# FPGAPower.net
KiCad netlist of a schematic drawn in Altium Designer
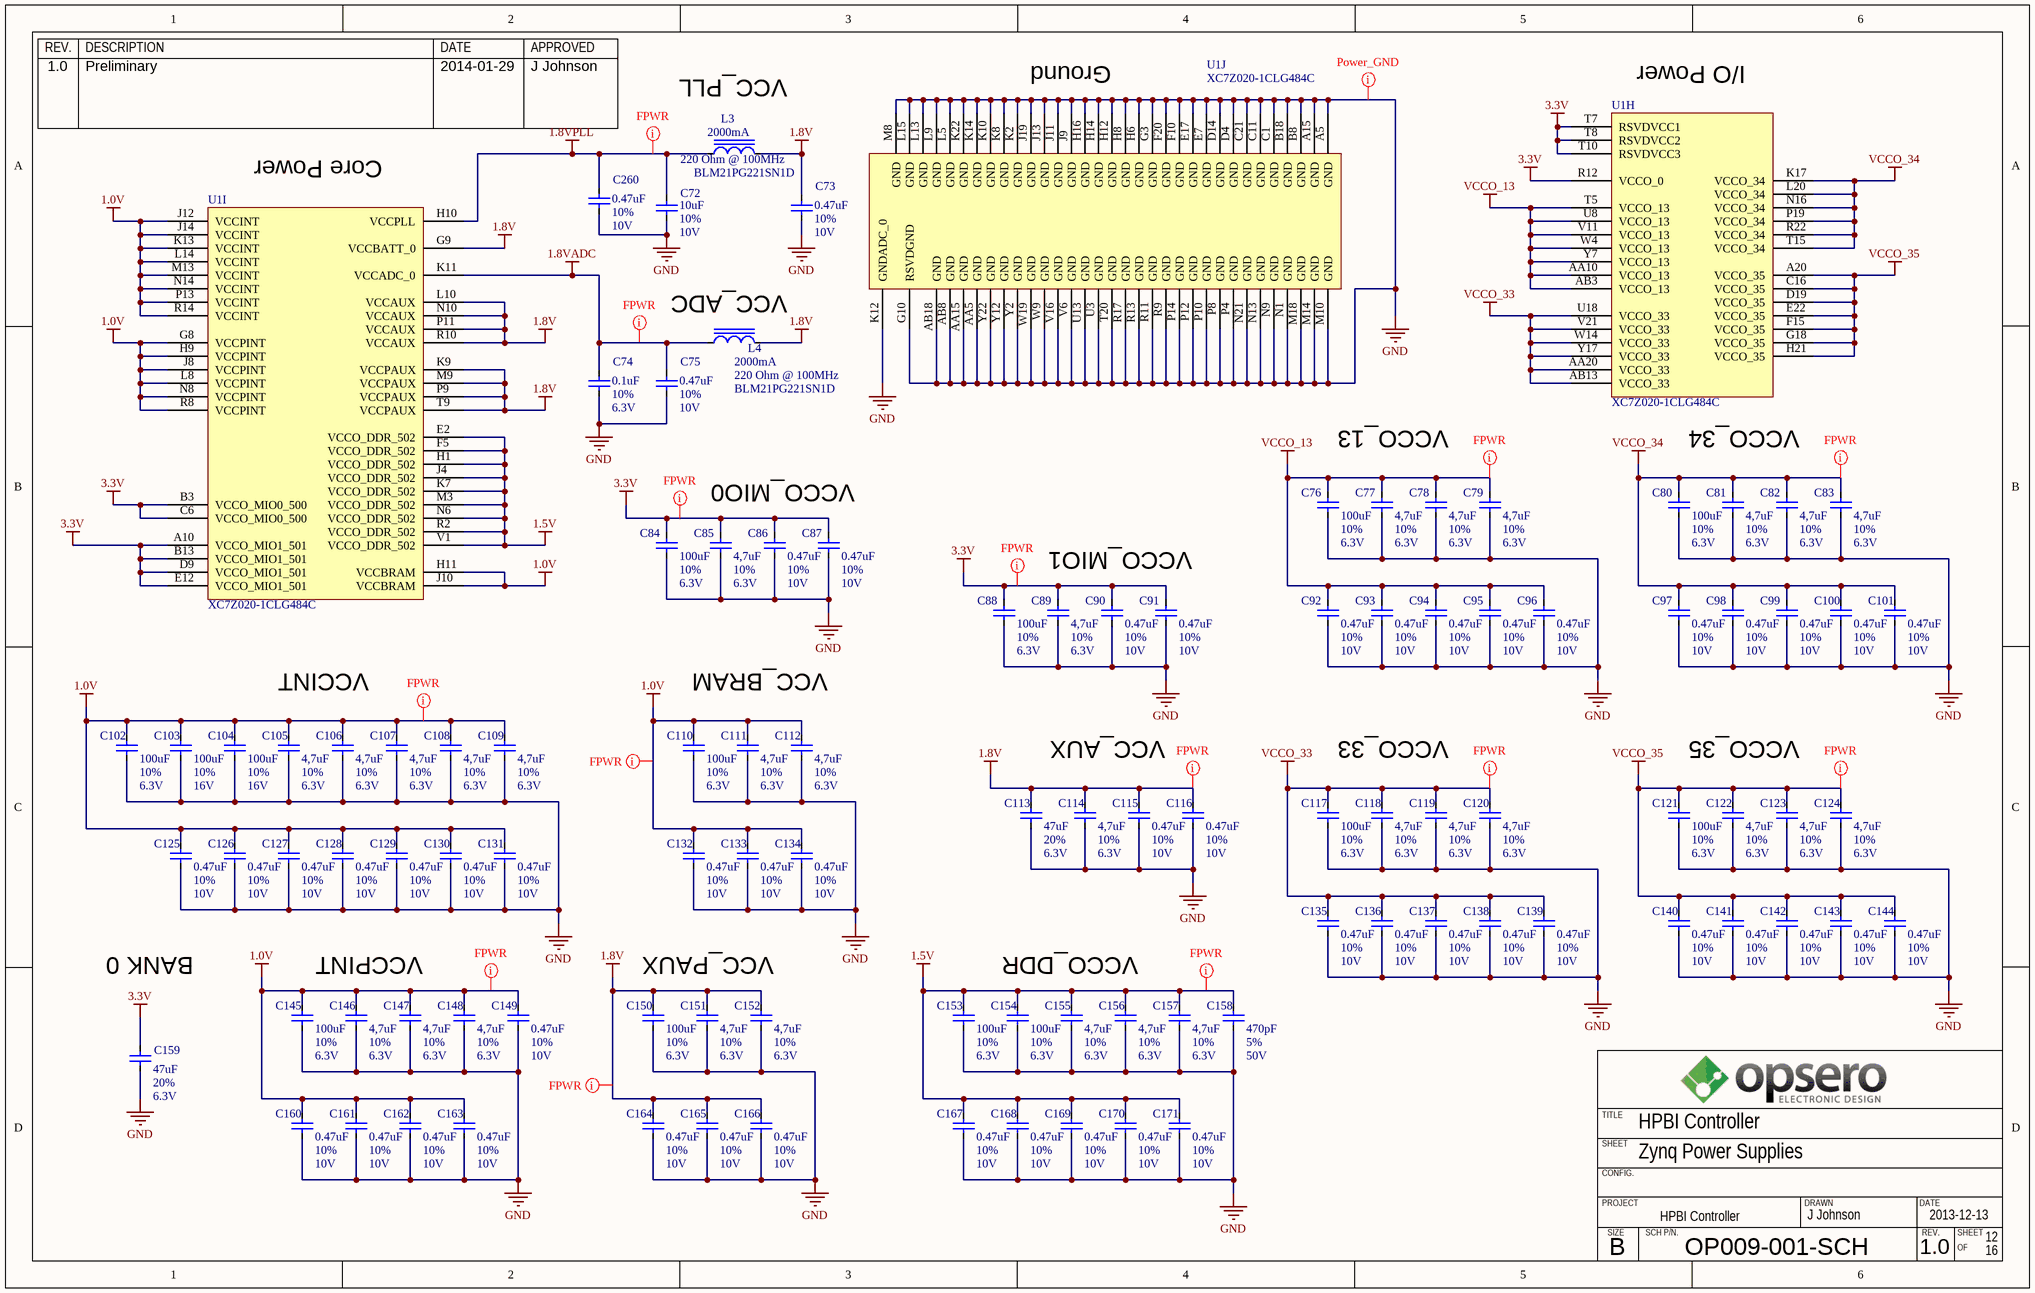
[diagram p0: FPGAPower.SchDoc]

(export (version "E")
  (design (tool "Eeschema 10.0.6"))
  (components
    (comp (ref "C72")
      (value "10uF")
      (footprint "CAPC1608X38N")
      (description "Capacitor ceramic, X5R, 10uF, 10V, 10%, -55 to +85 C, EIA0603")
      (fields
        (field (name "TOLERANCE") "10%")
        (field (name "VOLTAGE") "10V")
        (field (name "Comment") "CAPACITOR_NP_TYPE1")
      )
      (libsource (lib "parts") (part "CAPACITOR_NP_TYPE1"))
    )
    (comp (ref "C73")
      (value "0.47uF")
      (footprint "CAPC1005X55N")
      (description "Capacitor ceramic, X5R, 0.47uF, 10V, 10%, -55 to +85 C, EIA0402")
      (fields
        (field (name "TOLERANCE") "10%")
        (field (name "VOLTAGE") "10V")
        (field (name "Comment") "CAPACITOR_NP_TYPE1")
      )
      (libsource (lib "parts") (part "CAPACITOR_NP_TYPE1"))
    )
    (comp (ref "C74")
      (value "0.1uF")
      (footprint "CAPC0603X33N")
      (description "Capacitor ceramic, X5R, 0.1uF, 6.3V, 10%, -55 to +125 C, EIA0201")
      (fields
        (field (name "TOLERANCE") "10%")
        (field (name "VOLTAGE") "6.3V")
        (field (name "Comment") "CAPACITOR_NP_TYPE1")
      )
      (libsource (lib "parts") (part "CAPACITOR_NP_TYPE1"))
    )
    (comp (ref "C75")
      (value "0.47uF")
      (footprint "CAPC1005X55N")
      (description "Capacitor ceramic, X5R, 0.47uF, 10V, 10%, -55 to +85 C, EIA0402")
      (fields
        (field (name "TOLERANCE") "10%")
        (field (name "VOLTAGE") "10V")
        (field (name "Comment") "CAPACITOR_NP_TYPE1")
      )
      (libsource (lib "parts") (part "CAPACITOR_NP_TYPE1"))
    )
    (comp (ref "C76")
      (value "100uF")
      (footprint "CAPC3225X250N")
      (description "Capacitor ceramic, X5R, 100uF, 6.3V, 10%, -55 to +85 C, EIA1210")
      (fields
        (field (name "TOLERANCE") "10%")
        (field (name "VOLTAGE") "6.3V")
        (field (name "Comment") "CAPACITOR_NP_TYPE1")
      )
      (libsource (lib "parts") (part "CAPACITOR_NP_TYPE1"))
    )
    (comp (ref "C77")
      (value "4,7uF")
      (footprint "CAPC1005X33N")
      (description "Capacitor ceramic, X5R, 4,7uF, 6.3V, 10%, -55 to +85 C, EIA0402")
      (fields
        (field (name "TOLERANCE") "10%")
        (field (name "VOLTAGE") "6.3V")
        (field (name "Comment") "CAPACITOR_NP_TYPE1")
      )
      (libsource (lib "parts") (part "CAPACITOR_NP_TYPE1"))
    )
    (comp (ref "C78")
      (value "4,7uF")
      (footprint "CAPC1005X33N")
      (description "Capacitor ceramic, X5R, 4,7uF, 6.3V, 10%, -55 to +85 C, EIA0402")
      (fields
        (field (name "TOLERANCE") "10%")
        (field (name "VOLTAGE") "6.3V")
        (field (name "Comment") "CAPACITOR_NP_TYPE1")
      )
      (libsource (lib "parts") (part "CAPACITOR_NP_TYPE1"))
    )
    (comp (ref "C79")
      (value "4,7uF")
      (footprint "CAPC1005X33N")
      (description "Capacitor ceramic, X5R, 4,7uF, 6.3V, 10%, -55 to +85 C, EIA0402")
      (fields
        (field (name "TOLERANCE") "10%")
        (field (name "VOLTAGE") "6.3V")
        (field (name "Comment") "CAPACITOR_NP_TYPE1")
      )
      (libsource (lib "parts") (part "CAPACITOR_NP_TYPE1"))
    )
    (comp (ref "C80")
      (value "100uF")
      (footprint "CAPC3225X250N")
      (description "Capacitor ceramic, X5R, 100uF, 6.3V, 10%, -55 to +85 C, EIA1210")
      (fields
        (field (name "TOLERANCE") "10%")
        (field (name "VOLTAGE") "6.3V")
        (field (name "Comment") "CAPACITOR_NP_TYPE1")
      )
      (libsource (lib "parts") (part "CAPACITOR_NP_TYPE1"))
    )
    (comp (ref "C81")
      (value "4,7uF")
      (footprint "CAPC1005X33N")
      (description "Capacitor ceramic, X5R, 4,7uF, 6.3V, 10%, -55 to +85 C, EIA0402")
      (fields
        (field (name "TOLERANCE") "10%")
        (field (name "VOLTAGE") "6.3V")
        (field (name "Comment") "CAPACITOR_NP_TYPE1")
      )
      (libsource (lib "parts") (part "CAPACITOR_NP_TYPE1"))
    )
    (comp (ref "C82")
      (value "4,7uF")
      (footprint "CAPC1005X33N")
      (description "Capacitor ceramic, X5R, 4,7uF, 6.3V, 10%, -55 to +85 C, EIA0402")
      (fields
        (field (name "TOLERANCE") "10%")
        (field (name "VOLTAGE") "6.3V")
        (field (name "Comment") "CAPACITOR_NP_TYPE1")
      )
      (libsource (lib "parts") (part "CAPACITOR_NP_TYPE1"))
    )
    (comp (ref "C83")
      (value "4,7uF")
      (footprint "CAPC1005X33N")
      (description "Capacitor ceramic, X5R, 4,7uF, 6.3V, 10%, -55 to +85 C, EIA0402")
      (fields
        (field (name "TOLERANCE") "10%")
        (field (name "VOLTAGE") "6.3V")
        (field (name "Comment") "CAPACITOR_NP_TYPE1")
      )
      (libsource (lib "parts") (part "CAPACITOR_NP_TYPE1"))
    )
    (comp (ref "C84")
      (value "100uF")
      (footprint "CAPC3225X250N")
      (description "Capacitor ceramic, X5R, 100uF, 6.3V, 10%, -55 to +85 C, EIA1210")
      (fields
        (field (name "TOLERANCE") "10%")
        (field (name "VOLTAGE") "6.3V")
        (field (name "Comment") "CAPACITOR_NP_TYPE1")
      )
      (libsource (lib "parts") (part "CAPACITOR_NP_TYPE1"))
    )
    (comp (ref "C85")
      (value "4,7uF")
      (footprint "CAPC1005X33N")
      (description "Capacitor ceramic, X5R, 4,7uF, 6.3V, 10%, -55 to +85 C, EIA0402")
      (fields
        (field (name "TOLERANCE") "10%")
        (field (name "VOLTAGE") "6.3V")
        (field (name "Comment") "CAPACITOR_NP_TYPE1")
      )
      (libsource (lib "parts") (part "CAPACITOR_NP_TYPE1"))
    )
    (comp (ref "C86")
      (value "0.47uF")
      (footprint "CAPC1005X55N")
      (description "Capacitor ceramic, X5R, 0.47uF, 10V, 10%, -55 to +85 C, EIA0402")
      (fields
        (field (name "TOLERANCE") "10%")
        (field (name "VOLTAGE") "10V")
        (field (name "Comment") "CAPACITOR_NP_TYPE1")
      )
      (libsource (lib "parts") (part "CAPACITOR_NP_TYPE1"))
    )
    (comp (ref "C87")
      (value "0.47uF")
      (footprint "CAPC1005X55N")
      (description "Capacitor ceramic, X5R, 0.47uF, 10V, 10%, -55 to +85 C, EIA0402")
      (fields
        (field (name "TOLERANCE") "10%")
        (field (name "VOLTAGE") "10V")
        (field (name "Comment") "CAPACITOR_NP_TYPE1")
      )
      (libsource (lib "parts") (part "CAPACITOR_NP_TYPE1"))
    )
    (comp (ref "C88")
      (value "100uF")
      (footprint "CAPC3225X250N")
      (description "Capacitor ceramic, X5R, 100uF, 6.3V, 10%, -55 to +85 C, EIA1210")
      (fields
        (field (name "TOLERANCE") "10%")
        (field (name "VOLTAGE") "6.3V")
        (field (name "Comment") "CAPACITOR_NP_TYPE1")
      )
      (libsource (lib "parts") (part "CAPACITOR_NP_TYPE1"))
    )
    (comp (ref "C89")
      (value "4,7uF")
      (footprint "CAPC1005X33N")
      (description "Capacitor ceramic, X5R, 4,7uF, 6.3V, 10%, -55 to +85 C, EIA0402")
      (fields
        (field (name "TOLERANCE") "10%")
        (field (name "VOLTAGE") "6.3V")
        (field (name "Comment") "CAPACITOR_NP_TYPE1")
      )
      (libsource (lib "parts") (part "CAPACITOR_NP_TYPE1"))
    )
    (comp (ref "C90")
      (value "0.47uF")
      (footprint "CAPC1005X55N")
      (description "Capacitor ceramic, X5R, 0.47uF, 10V, 10%, -55 to +85 C, EIA0402")
      (fields
        (field (name "TOLERANCE") "10%")
        (field (name "VOLTAGE") "10V")
        (field (name "Comment") "CAPACITOR_NP_TYPE1")
      )
      (libsource (lib "parts") (part "CAPACITOR_NP_TYPE1"))
    )
    (comp (ref "C91")
      (value "0.47uF")
      (footprint "CAPC1005X55N")
      (description "Capacitor ceramic, X5R, 0.47uF, 10V, 10%, -55 to +85 C, EIA0402")
      (fields
        (field (name "TOLERANCE") "10%")
        (field (name "VOLTAGE") "10V")
        (field (name "Comment") "CAPACITOR_NP_TYPE1")
      )
      (libsource (lib "parts") (part "CAPACITOR_NP_TYPE1"))
    )
    (comp (ref "C92")
      (value "0.47uF")
      (footprint "CAPC1005X55N")
      (description "Capacitor ceramic, X5R, 0.47uF, 10V, 10%, -55 to +85 C, EIA0402")
      (fields
        (field (name "TOLERANCE") "10%")
        (field (name "VOLTAGE") "10V")
        (field (name "Comment") "CAPACITOR_NP_TYPE1")
      )
      (libsource (lib "parts") (part "CAPACITOR_NP_TYPE1"))
    )
    (comp (ref "C93")
      (value "0.47uF")
      (footprint "CAPC1005X55N")
      (description "Capacitor ceramic, X5R, 0.47uF, 10V, 10%, -55 to +85 C, EIA0402")
      (fields
        (field (name "TOLERANCE") "10%")
        (field (name "VOLTAGE") "10V")
        (field (name "Comment") "CAPACITOR_NP_TYPE1")
      )
      (libsource (lib "parts") (part "CAPACITOR_NP_TYPE1"))
    )
    (comp (ref "C94")
      (value "0.47uF")
      (footprint "CAPC1005X55N")
      (description "Capacitor ceramic, X5R, 0.47uF, 10V, 10%, -55 to +85 C, EIA0402")
      (fields
        (field (name "TOLERANCE") "10%")
        (field (name "VOLTAGE") "10V")
        (field (name "Comment") "CAPACITOR_NP_TYPE1")
      )
      (libsource (lib "parts") (part "CAPACITOR_NP_TYPE1"))
    )
    (comp (ref "C95")
      (value "0.47uF")
      (footprint "CAPC1005X55N")
      (description "Capacitor ceramic, X5R, 0.47uF, 10V, 10%, -55 to +85 C, EIA0402")
      (fields
        (field (name "TOLERANCE") "10%")
        (field (name "VOLTAGE") "10V")
        (field (name "Comment") "CAPACITOR_NP_TYPE1")
      )
      (libsource (lib "parts") (part "CAPACITOR_NP_TYPE1"))
    )
    (comp (ref "C96")
      (value "0.47uF")
      (footprint "CAPC1005X55N")
      (description "Capacitor ceramic, X5R, 0.47uF, 10V, 10%, -55 to +85 C, EIA0402")
      (fields
        (field (name "TOLERANCE") "10%")
        (field (name "VOLTAGE") "10V")
        (field (name "Comment") "CAPACITOR_NP_TYPE1")
      )
      (libsource (lib "parts") (part "CAPACITOR_NP_TYPE1"))
    )
    (comp (ref "C97")
      (value "0.47uF")
      (footprint "CAPC1005X55N")
      (description "Capacitor ceramic, X5R, 0.47uF, 10V, 10%, -55 to +85 C, EIA0402")
      (fields
        (field (name "TOLERANCE") "10%")
        (field (name "VOLTAGE") "10V")
        (field (name "Comment") "CAPACITOR_NP_TYPE1")
      )
      (libsource (lib "parts") (part "CAPACITOR_NP_TYPE1"))
    )
    (comp (ref "C98")
      (value "0.47uF")
      (footprint "CAPC1005X55N")
      (description "Capacitor ceramic, X5R, 0.47uF, 10V, 10%, -55 to +85 C, EIA0402")
      (fields
        (field (name "TOLERANCE") "10%")
        (field (name "VOLTAGE") "10V")
        (field (name "Comment") "CAPACITOR_NP_TYPE1")
      )
      (libsource (lib "parts") (part "CAPACITOR_NP_TYPE1"))
    )
    (comp (ref "C99")
      (value "0.47uF")
      (footprint "CAPC1005X55N")
      (description "Capacitor ceramic, X5R, 0.47uF, 10V, 10%, -55 to +85 C, EIA0402")
      (fields
        (field (name "TOLERANCE") "10%")
        (field (name "VOLTAGE") "10V")
        (field (name "Comment") "CAPACITOR_NP_TYPE1")
      )
      (libsource (lib "parts") (part "CAPACITOR_NP_TYPE1"))
    )
    (comp (ref "C100")
      (value "0.47uF")
      (footprint "CAPC1005X55N")
      (description "Capacitor ceramic, X5R, 0.47uF, 10V, 10%, -55 to +85 C, EIA0402")
      (fields
        (field (name "TOLERANCE") "10%")
        (field (name "VOLTAGE") "10V")
        (field (name "Comment") "CAPACITOR_NP_TYPE1")
      )
      (libsource (lib "parts") (part "CAPACITOR_NP_TYPE1"))
    )
    (comp (ref "C101")
      (value "0.47uF")
      (footprint "CAPC1005X55N")
      (description "Capacitor ceramic, X5R, 0.47uF, 10V, 10%, -55 to +85 C, EIA0402")
      (fields
        (field (name "TOLERANCE") "10%")
        (field (name "VOLTAGE") "10V")
        (field (name "Comment") "CAPACITOR_NP_TYPE1")
      )
      (libsource (lib "parts") (part "CAPACITOR_NP_TYPE1"))
    )
    (comp (ref "C102")
      (value "100uF")
      (footprint "CAPC3225X250N")
      (description "Capacitor ceramic, X5R, 100uF, 6.3V, 10%, -55 to +85 C, EIA1210")
      (fields
        (field (name "TOLERANCE") "10%")
        (field (name "VOLTAGE") "6.3V")
        (field (name "Comment") "CAPACITOR_NP_TYPE1")
      )
      (libsource (lib "parts") (part "CAPACITOR_NP_TYPE1"))
    )
    (comp (ref "C103")
      (value "100uF")
      (footprint "CAPC3225X250N")
      (description "Capacitor ceramic, X5R, 100uF, 16V, 10%, -55 to +85 C, EIA1210")
      (fields
        (field (name "TOLERANCE") "10%")
        (field (name "VOLTAGE") "16V")
        (field (name "Comment") "CAPACITOR_NP_TYPE1")
      )
      (libsource (lib "parts") (part "CAPACITOR_NP_TYPE1"))
    )
    (comp (ref "C104")
      (value "100uF")
      (footprint "CAPC3225X250N")
      (description "Capacitor ceramic, X5R, 100uF, 16V, 10%, -55 to +85 C, EIA1210")
      (fields
        (field (name "TOLERANCE") "10%")
        (field (name "VOLTAGE") "16V")
        (field (name "Comment") "CAPACITOR_NP_TYPE1")
      )
      (libsource (lib "parts") (part "CAPACITOR_NP_TYPE1"))
    )
    (comp (ref "C105")
      (value "4,7uF")
      (footprint "CAPC1005X33N")
      (description "Capacitor ceramic, X5R, 4,7uF, 6.3V, 10%, -55 to +85 C, EIA0402")
      (fields
        (field (name "TOLERANCE") "10%")
        (field (name "VOLTAGE") "6.3V")
        (field (name "Comment") "CAPACITOR_NP_TYPE1")
      )
      (libsource (lib "parts") (part "CAPACITOR_NP_TYPE1"))
    )
    (comp (ref "C106")
      (value "4,7uF")
      (footprint "CAPC1005X33N")
      (description "Capacitor ceramic, X5R, 4,7uF, 6.3V, 10%, -55 to +85 C, EIA0402")
      (fields
        (field (name "TOLERANCE") "10%")
        (field (name "VOLTAGE") "6.3V")
        (field (name "Comment") "CAPACITOR_NP_TYPE1")
      )
      (libsource (lib "parts") (part "CAPACITOR_NP_TYPE1"))
    )
    (comp (ref "C107")
      (value "4,7uF")
      (footprint "CAPC1005X33N")
      (description "Capacitor ceramic, X5R, 4,7uF, 6.3V, 10%, -55 to +85 C, EIA0402")
      (fields
        (field (name "TOLERANCE") "10%")
        (field (name "VOLTAGE") "6.3V")
        (field (name "Comment") "CAPACITOR_NP_TYPE1")
      )
      (libsource (lib "parts") (part "CAPACITOR_NP_TYPE1"))
    )
    (comp (ref "C108")
      (value "4,7uF")
      (footprint "CAPC1005X33N")
      (description "Capacitor ceramic, X5R, 4,7uF, 6.3V, 10%, -55 to +85 C, EIA0402")
      (fields
        (field (name "TOLERANCE") "10%")
        (field (name "VOLTAGE") "6.3V")
        (field (name "Comment") "CAPACITOR_NP_TYPE1")
      )
      (libsource (lib "parts") (part "CAPACITOR_NP_TYPE1"))
    )
    (comp (ref "C109")
      (value "4,7uF")
      (footprint "CAPC1005X33N")
      (description "Capacitor ceramic, X5R, 4,7uF, 6.3V, 10%, -55 to +85 C, EIA0402")
      (fields
        (field (name "TOLERANCE") "10%")
        (field (name "VOLTAGE") "6.3V")
        (field (name "Comment") "CAPACITOR_NP_TYPE1")
      )
      (libsource (lib "parts") (part "CAPACITOR_NP_TYPE1"))
    )
    (comp (ref "C110")
      (value "100uF")
      (footprint "CAPC3225X250N")
      (description "Capacitor ceramic, X5R, 100uF, 6.3V, 10%, -55 to +85 C, EIA1210")
      (fields
        (field (name "TOLERANCE") "10%")
        (field (name "VOLTAGE") "6.3V")
        (field (name "Comment") "CAPACITOR_NP_TYPE1")
      )
      (libsource (lib "parts") (part "CAPACITOR_NP_TYPE1"))
    )
    (comp (ref "C111")
      (value "4,7uF")
      (footprint "CAPC1005X33N")
      (description "Capacitor ceramic, X5R, 4,7uF, 6.3V, 10%, -55 to +85 C, EIA0402")
      (fields
        (field (name "TOLERANCE") "10%")
        (field (name "VOLTAGE") "6.3V")
        (field (name "Comment") "CAPACITOR_NP_TYPE1")
      )
      (libsource (lib "parts") (part "CAPACITOR_NP_TYPE1"))
    )
    (comp (ref "C112")
      (value "4,7uF")
      (footprint "CAPC1005X33N")
      (description "Capacitor ceramic, X5R, 4,7uF, 6.3V, 10%, -55 to +85 C, EIA0402")
      (fields
        (field (name "TOLERANCE") "10%")
        (field (name "VOLTAGE") "6.3V")
        (field (name "Comment") "CAPACITOR_NP_TYPE1")
      )
      (libsource (lib "parts") (part "CAPACITOR_NP_TYPE1"))
    )
    (comp (ref "C113")
      (value "47uF")
      (footprint "CAPC2013X125N")
      (description "Capacitor ceramic, X5R, 47uF, 6.3V, 20%, -55 to +85 C,")
      (fields
        (field (name "TOLERANCE") "20%")
        (field (name "VOLTAGE") "6.3V")
        (field (name "Comment") "CAPACITOR_NP_TYPE1")
      )
      (libsource (lib "parts") (part "CAPACITOR_NP_TYPE1"))
    )
    (comp (ref "C114")
      (value "4,7uF")
      (footprint "CAPC1005X33N")
      (description "Capacitor ceramic, X5R, 4,7uF, 6.3V, 10%, -55 to +85 C, EIA0402")
      (fields
        (field (name "TOLERANCE") "10%")
        (field (name "VOLTAGE") "6.3V")
        (field (name "Comment") "CAPACITOR_NP_TYPE1")
      )
      (libsource (lib "parts") (part "CAPACITOR_NP_TYPE1"))
    )
    (comp (ref "C115")
      (value "0.47uF")
      (footprint "CAPC1005X55N")
      (description "Capacitor ceramic, X5R, 0.47uF, 10V, 10%, -55 to +85 C, EIA0402")
      (fields
        (field (name "TOLERANCE") "10%")
        (field (name "VOLTAGE") "10V")
        (field (name "Comment") "CAPACITOR_NP_TYPE1")
      )
      (libsource (lib "parts") (part "CAPACITOR_NP_TYPE1"))
    )
    (comp (ref "C116")
      (value "0.47uF")
      (footprint "CAPC1005X55N")
      (description "Capacitor ceramic, X5R, 0.47uF, 10V, 10%, -55 to +85 C, EIA0402")
      (fields
        (field (name "TOLERANCE") "10%")
        (field (name "VOLTAGE") "10V")
        (field (name "Comment") "CAPACITOR_NP_TYPE1")
      )
      (libsource (lib "parts") (part "CAPACITOR_NP_TYPE1"))
    )
    (comp (ref "C117")
      (value "100uF")
      (footprint "CAPC3225X250N")
      (description "Capacitor ceramic, X5R, 100uF, 6.3V, 10%, -55 to +85 C, EIA1210")
      (fields
        (field (name "TOLERANCE") "10%")
        (field (name "VOLTAGE") "6.3V")
        (field (name "Comment") "CAPACITOR_NP_TYPE1")
      )
      (libsource (lib "parts") (part "CAPACITOR_NP_TYPE1"))
    )
    (comp (ref "C118")
      (value "4,7uF")
      (footprint "CAPC1005X33N")
      (description "Capacitor ceramic, X5R, 4,7uF, 6.3V, 10%, -55 to +85 C, EIA0402")
      (fields
        (field (name "TOLERANCE") "10%")
        (field (name "VOLTAGE") "6.3V")
        (field (name "Comment") "CAPACITOR_NP_TYPE1")
      )
      (libsource (lib "parts") (part "CAPACITOR_NP_TYPE1"))
    )
    (comp (ref "C119")
      (value "4,7uF")
      (footprint "CAPC1005X33N")
      (description "Capacitor ceramic, X5R, 4,7uF, 6.3V, 10%, -55 to +85 C, EIA0402")
      (fields
        (field (name "TOLERANCE") "10%")
        (field (name "VOLTAGE") "6.3V")
        (field (name "Comment") "CAPACITOR_NP_TYPE1")
      )
      (libsource (lib "parts") (part "CAPACITOR_NP_TYPE1"))
    )
    (comp (ref "C120")
      (value "4,7uF")
      (footprint "CAPC1005X33N")
      (description "Capacitor ceramic, X5R, 4,7uF, 6.3V, 10%, -55 to +85 C, EIA0402")
      (fields
        (field (name "TOLERANCE") "10%")
        (field (name "VOLTAGE") "6.3V")
        (field (name "Comment") "CAPACITOR_NP_TYPE1")
      )
      (libsource (lib "parts") (part "CAPACITOR_NP_TYPE1"))
    )
    (comp (ref "C121")
      (value "100uF")
      (footprint "CAPC3225X250N")
      (description "Capacitor ceramic, X5R, 100uF, 6.3V, 10%, -55 to +85 C, EIA1210")
      (fields
        (field (name "TOLERANCE") "10%")
        (field (name "VOLTAGE") "6.3V")
        (field (name "Comment") "CAPACITOR_NP_TYPE1")
      )
      (libsource (lib "parts") (part "CAPACITOR_NP_TYPE1"))
    )
    (comp (ref "C122")
      (value "4,7uF")
      (footprint "CAPC1005X33N")
      (description "Capacitor ceramic, X5R, 4,7uF, 6.3V, 10%, -55 to +85 C, EIA0402")
      (fields
        (field (name "TOLERANCE") "10%")
        (field (name "VOLTAGE") "6.3V")
        (field (name "Comment") "CAPACITOR_NP_TYPE1")
      )
      (libsource (lib "parts") (part "CAPACITOR_NP_TYPE1"))
    )
    (comp (ref "C123")
      (value "4,7uF")
      (footprint "CAPC1005X33N")
      (description "Capacitor ceramic, X5R, 4,7uF, 6.3V, 10%, -55 to +85 C, EIA0402")
      (fields
        (field (name "TOLERANCE") "10%")
        (field (name "VOLTAGE") "6.3V")
        (field (name "Comment") "CAPACITOR_NP_TYPE1")
      )
      (libsource (lib "parts") (part "CAPACITOR_NP_TYPE1"))
    )
    (comp (ref "C124")
      (value "4,7uF")
      (footprint "CAPC1005X33N")
      (description "Capacitor ceramic, X5R, 4,7uF, 6.3V, 10%, -55 to +85 C, EIA0402")
      (fields
        (field (name "TOLERANCE") "10%")
        (field (name "VOLTAGE") "6.3V")
        (field (name "Comment") "CAPACITOR_NP_TYPE1")
      )
      (libsource (lib "parts") (part "CAPACITOR_NP_TYPE1"))
    )
    (comp (ref "C125")
      (value "0.47uF")
      (footprint "CAPC1005X55N")
      (description "Capacitor ceramic, X5R, 0.47uF, 10V, 10%, -55 to +85 C, EIA0402")
      (fields
        (field (name "TOLERANCE") "10%")
        (field (name "VOLTAGE") "10V")
        (field (name "Comment") "CAPACITOR_NP_TYPE1")
      )
      (libsource (lib "parts") (part "CAPACITOR_NP_TYPE1"))
    )
    (comp (ref "C126")
      (value "0.47uF")
      (footprint "CAPC1005X55N")
      (description "Capacitor ceramic, X5R, 0.47uF, 10V, 10%, -55 to +85 C, EIA0402")
      (fields
        (field (name "TOLERANCE") "10%")
        (field (name "VOLTAGE") "10V")
        (field (name "Comment") "CAPACITOR_NP_TYPE1")
      )
      (libsource (lib "parts") (part "CAPACITOR_NP_TYPE1"))
    )
    (comp (ref "C127")
      (value "0.47uF")
      (footprint "CAPC1005X55N")
      (description "Capacitor ceramic, X5R, 0.47uF, 10V, 10%, -55 to +85 C, EIA0402")
      (fields
        (field (name "TOLERANCE") "10%")
        (field (name "VOLTAGE") "10V")
        (field (name "Comment") "CAPACITOR_NP_TYPE1")
      )
      (libsource (lib "parts") (part "CAPACITOR_NP_TYPE1"))
    )
    (comp (ref "C128")
      (value "0.47uF")
      (footprint "CAPC1005X55N")
      (description "Capacitor ceramic, X5R, 0.47uF, 10V, 10%, -55 to +85 C, EIA0402")
      (fields
        (field (name "TOLERANCE") "10%")
        (field (name "VOLTAGE") "10V")
        (field (name "Comment") "CAPACITOR_NP_TYPE1")
      )
      (libsource (lib "parts") (part "CAPACITOR_NP_TYPE1"))
    )
    (comp (ref "C129")
      (value "0.47uF")
      (footprint "CAPC1005X55N")
      (description "Capacitor ceramic, X5R, 0.47uF, 10V, 10%, -55 to +85 C, EIA0402")
      (fields
        (field (name "TOLERANCE") "10%")
        (field (name "VOLTAGE") "10V")
        (field (name "Comment") "CAPACITOR_NP_TYPE1")
      )
      (libsource (lib "parts") (part "CAPACITOR_NP_TYPE1"))
    )
    (comp (ref "C130")
      (value "0.47uF")
      (footprint "CAPC1005X55N")
      (description "Capacitor ceramic, X5R, 0.47uF, 10V, 10%, -55 to +85 C, EIA0402")
      (fields
        (field (name "TOLERANCE") "10%")
        (field (name "VOLTAGE") "10V")
        (field (name "Comment") "CAPACITOR_NP_TYPE1")
      )
      (libsource (lib "parts") (part "CAPACITOR_NP_TYPE1"))
    )
    (comp (ref "C131")
      (value "0.47uF")
      (footprint "CAPC1005X55N")
      (description "Capacitor ceramic, X5R, 0.47uF, 10V, 10%, -55 to +85 C, EIA0402")
      (fields
        (field (name "TOLERANCE") "10%")
        (field (name "VOLTAGE") "10V")
        (field (name "Comment") "CAPACITOR_NP_TYPE1")
      )
      (libsource (lib "parts") (part "CAPACITOR_NP_TYPE1"))
    )
    (comp (ref "C132")
      (value "0.47uF")
      (footprint "CAPC1005X55N")
      (description "Capacitor ceramic, X5R, 0.47uF, 10V, 10%, -55 to +85 C, EIA0402")
      (fields
        (field (name "TOLERANCE") "10%")
        (field (name "VOLTAGE") "10V")
        (field (name "Comment") "CAPACITOR_NP_TYPE1")
      )
      (libsource (lib "parts") (part "CAPACITOR_NP_TYPE1"))
    )
    (comp (ref "C133")
      (value "0.47uF")
      (footprint "CAPC1005X55N")
      (description "Capacitor ceramic, X5R, 0.47uF, 10V, 10%, -55 to +85 C, EIA0402")
      (fields
        (field (name "TOLERANCE") "10%")
        (field (name "VOLTAGE") "10V")
        (field (name "Comment") "CAPACITOR_NP_TYPE1")
      )
      (libsource (lib "parts") (part "CAPACITOR_NP_TYPE1"))
    )
    (comp (ref "C134")
      (value "0.47uF")
      (footprint "CAPC1005X55N")
      (description "Capacitor ceramic, X5R, 0.47uF, 10V, 10%, -55 to +85 C, EIA0402")
      (fields
        (field (name "TOLERANCE") "10%")
        (field (name "VOLTAGE") "10V")
        (field (name "Comment") "CAPACITOR_NP_TYPE1")
      )
      (libsource (lib "parts") (part "CAPACITOR_NP_TYPE1"))
    )
    (comp (ref "C135")
      (value "0.47uF")
      (footprint "CAPC1005X55N")
      (description "Capacitor ceramic, X5R, 0.47uF, 10V, 10%, -55 to +85 C, EIA0402")
      (fields
        (field (name "TOLERANCE") "10%")
        (field (name "VOLTAGE") "10V")
        (field (name "Comment") "CAPACITOR_NP_TYPE1")
      )
      (libsource (lib "parts") (part "CAPACITOR_NP_TYPE1"))
    )
    (comp (ref "C136")
      (value "0.47uF")
      (footprint "CAPC1005X55N")
      (description "Capacitor ceramic, X5R, 0.47uF, 10V, 10%, -55 to +85 C, EIA0402")
      (fields
        (field (name "TOLERANCE") "10%")
        (field (name "VOLTAGE") "10V")
        (field (name "Comment") "CAPACITOR_NP_TYPE1")
      )
      (libsource (lib "parts") (part "CAPACITOR_NP_TYPE1"))
    )
    (comp (ref "C137")
      (value "0.47uF")
      (footprint "CAPC1005X55N")
      (description "Capacitor ceramic, X5R, 0.47uF, 10V, 10%, -55 to +85 C, EIA0402")
      (fields
        (field (name "TOLERANCE") "10%")
        (field (name "VOLTAGE") "10V")
        (field (name "Comment") "CAPACITOR_NP_TYPE1")
      )
      (libsource (lib "parts") (part "CAPACITOR_NP_TYPE1"))
    )
    (comp (ref "C138")
      (value "0.47uF")
      (footprint "CAPC1005X55N")
      (description "Capacitor ceramic, X5R, 0.47uF, 10V, 10%, -55 to +85 C, EIA0402")
      (fields
        (field (name "TOLERANCE") "10%")
        (field (name "VOLTAGE") "10V")
        (field (name "Comment") "CAPACITOR_NP_TYPE1")
      )
      (libsource (lib "parts") (part "CAPACITOR_NP_TYPE1"))
    )
    (comp (ref "C139")
      (value "0.47uF")
      (footprint "CAPC1005X55N")
      (description "Capacitor ceramic, X5R, 0.47uF, 10V, 10%, -55 to +85 C, EIA0402")
      (fields
        (field (name "TOLERANCE") "10%")
        (field (name "VOLTAGE") "10V")
        (field (name "Comment") "CAPACITOR_NP_TYPE1")
      )
      (libsource (lib "parts") (part "CAPACITOR_NP_TYPE1"))
    )
    (comp (ref "C140")
      (value "0.47uF")
      (footprint "CAPC1005X55N")
      (description "Capacitor ceramic, X5R, 0.47uF, 10V, 10%, -55 to +85 C, EIA0402")
      (fields
        (field (name "TOLERANCE") "10%")
        (field (name "VOLTAGE") "10V")
        (field (name "Comment") "CAPACITOR_NP_TYPE1")
      )
      (libsource (lib "parts") (part "CAPACITOR_NP_TYPE1"))
    )
    (comp (ref "C141")
      (value "0.47uF")
      (footprint "CAPC1005X55N")
      (description "Capacitor ceramic, X5R, 0.47uF, 10V, 10%, -55 to +85 C, EIA0402")
      (fields
        (field (name "TOLERANCE") "10%")
        (field (name "VOLTAGE") "10V")
        (field (name "Comment") "CAPACITOR_NP_TYPE1")
      )
      (libsource (lib "parts") (part "CAPACITOR_NP_TYPE1"))
    )
    (comp (ref "C142")
      (value "0.47uF")
      (footprint "CAPC1005X55N")
      (description "Capacitor ceramic, X5R, 0.47uF, 10V, 10%, -55 to +85 C, EIA0402")
      (fields
        (field (name "TOLERANCE") "10%")
        (field (name "VOLTAGE") "10V")
        (field (name "Comment") "CAPACITOR_NP_TYPE1")
      )
      (libsource (lib "parts") (part "CAPACITOR_NP_TYPE1"))
    )
    (comp (ref "C143")
      (value "0.47uF")
      (footprint "CAPC1005X55N")
      (description "Capacitor ceramic, X5R, 0.47uF, 10V, 10%, -55 to +85 C, EIA0402")
      (fields
        (field (name "TOLERANCE") "10%")
        (field (name "VOLTAGE") "10V")
        (field (name "Comment") "CAPACITOR_NP_TYPE1")
      )
      (libsource (lib "parts") (part "CAPACITOR_NP_TYPE1"))
    )
    (comp (ref "C144")
      (value "0.47uF")
      (footprint "CAPC1005X55N")
      (description "Capacitor ceramic, X5R, 0.47uF, 10V, 10%, -55 to +85 C, EIA0402")
      (fields
        (field (name "TOLERANCE") "10%")
        (field (name "VOLTAGE") "10V")
        (field (name "Comment") "CAPACITOR_NP_TYPE1")
      )
      (libsource (lib "parts") (part "CAPACITOR_NP_TYPE1"))
    )
    (comp (ref "C145")
      (value "100uF")
      (footprint "CAPC3225X250N")
      (description "Capacitor ceramic, X5R, 100uF, 6.3V, 10%, -55 to +85 C, EIA1210")
      (fields
        (field (name "TOLERANCE") "10%")
        (field (name "VOLTAGE") "6.3V")
        (field (name "Comment") "CAPACITOR_NP_TYPE1")
      )
      (libsource (lib "parts") (part "CAPACITOR_NP_TYPE1"))
    )
    (comp (ref "C146")
      (value "4,7uF")
      (footprint "CAPC1005X33N")
      (description "Capacitor ceramic, X5R, 4,7uF, 6.3V, 10%, -55 to +85 C, EIA0402")
      (fields
        (field (name "TOLERANCE") "10%")
        (field (name "VOLTAGE") "6.3V")
        (field (name "Comment") "CAPACITOR_NP_TYPE1")
      )
      (libsource (lib "parts") (part "CAPACITOR_NP_TYPE1"))
    )
    (comp (ref "C147")
      (value "4,7uF")
      (footprint "CAPC1005X33N")
      (description "Capacitor ceramic, X5R, 4,7uF, 6.3V, 10%, -55 to +85 C, EIA0402")
      (fields
        (field (name "TOLERANCE") "10%")
        (field (name "VOLTAGE") "6.3V")
        (field (name "Comment") "CAPACITOR_NP_TYPE1")
      )
      (libsource (lib "parts") (part "CAPACITOR_NP_TYPE1"))
    )
    (comp (ref "C148")
      (value "4,7uF")
      (footprint "CAPC1005X33N")
      (description "Capacitor ceramic, X5R, 4,7uF, 6.3V, 10%, -55 to +85 C, EIA0402")
      (fields
        (field (name "TOLERANCE") "10%")
        (field (name "VOLTAGE") "6.3V")
        (field (name "Comment") "CAPACITOR_NP_TYPE1")
      )
      (libsource (lib "parts") (part "CAPACITOR_NP_TYPE1"))
    )
    (comp (ref "C149")
      (value "0.47uF")
      (footprint "CAPC1005X55N")
      (description "Capacitor ceramic, X5R, 0.47uF, 10V, 10%, -55 to +85 C, EIA0402")
      (fields
        (field (name "TOLERANCE") "10%")
        (field (name "VOLTAGE") "10V")
        (field (name "Comment") "CAPACITOR_NP_TYPE1")
      )
      (libsource (lib "parts") (part "CAPACITOR_NP_TYPE1"))
    )
    (comp (ref "C150")
      (value "100uF")
      (footprint "CAPC3225X250N")
      (description "Capacitor ceramic, X5R, 100uF, 6.3V, 10%, -55 to +85 C, EIA1210")
      (fields
        (field (name "TOLERANCE") "10%")
        (field (name "VOLTAGE") "6.3V")
        (field (name "Comment") "CAPACITOR_NP_TYPE1")
      )
      (libsource (lib "parts") (part "CAPACITOR_NP_TYPE1"))
    )
    (comp (ref "C151")
      (value "4,7uF")
      (footprint "CAPC1005X33N")
      (description "Capacitor ceramic, X5R, 4,7uF, 6.3V, 10%, -55 to +85 C, EIA0402")
      (fields
        (field (name "TOLERANCE") "10%")
        (field (name "VOLTAGE") "6.3V")
        (field (name "Comment") "CAPACITOR_NP_TYPE1")
      )
      (libsource (lib "parts") (part "CAPACITOR_NP_TYPE1"))
    )
    (comp (ref "C152")
      (value "4,7uF")
      (footprint "CAPC1005X33N")
      (description "Capacitor ceramic, X5R, 4,7uF, 6.3V, 10%, -55 to +85 C, EIA0402")
      (fields
        (field (name "TOLERANCE") "10%")
        (field (name "VOLTAGE") "6.3V")
        (field (name "Comment") "CAPACITOR_NP_TYPE1")
      )
      (libsource (lib "parts") (part "CAPACITOR_NP_TYPE1"))
    )
    (comp (ref "C153")
      (value "100uF")
      (footprint "CAPC3225X250N")
      (description "Capacitor ceramic, X5R, 100uF, 6.3V, 10%, -55 to +85 C, EIA1210")
      (fields
        (field (name "TOLERANCE") "10%")
        (field (name "VOLTAGE") "6.3V")
        (field (name "Comment") "CAPACITOR_NP_TYPE1")
      )
      (libsource (lib "parts") (part "CAPACITOR_NP_TYPE1"))
    )
    (comp (ref "C154")
      (value "100uF")
      (footprint "CAPC3225X250N")
      (description "Capacitor ceramic, X5R, 100uF, 6.3V, 10%, -55 to +85 C, EIA1210")
      (fields
        (field (name "TOLERANCE") "10%")
        (field (name "VOLTAGE") "6.3V")
        (field (name "Comment") "CAPACITOR_NP_TYPE1")
      )
      (libsource (lib "parts") (part "CAPACITOR_NP_TYPE1"))
    )
    (comp (ref "C155")
      (value "4,7uF")
      (footprint "CAPC1005X33N")
      (description "Capacitor ceramic, X5R, 4,7uF, 6.3V, 10%, -55 to +85 C, EIA0402")
      (fields
        (field (name "TOLERANCE") "10%")
        (field (name "VOLTAGE") "6.3V")
        (field (name "Comment") "CAPACITOR_NP_TYPE1")
      )
      (libsource (lib "parts") (part "CAPACITOR_NP_TYPE1"))
    )
    (comp (ref "C156")
      (value "4,7uF")
      (footprint "CAPC1005X33N")
      (description "Capacitor ceramic, X5R, 4,7uF, 6.3V, 10%, -55 to +85 C, EIA0402")
      (fields
        (field (name "TOLERANCE") "10%")
        (field (name "VOLTAGE") "6.3V")
        (field (name "Comment") "CAPACITOR_NP_TYPE1")
      )
      (libsource (lib "parts") (part "CAPACITOR_NP_TYPE1"))
    )
    (comp (ref "C157")
      (value "4,7uF")
      (footprint "CAPC1005X33N")
      (description "Capacitor ceramic, X5R, 4,7uF, 6.3V, 10%, -55 to +85 C, EIA0402")
      (fields
        (field (name "TOLERANCE") "10%")
        (field (name "VOLTAGE") "6.3V")
        (field (name "Comment") "CAPACITOR_NP_TYPE1")
      )
      (libsource (lib "parts") (part "CAPACITOR_NP_TYPE1"))
    )
    (comp (ref "C158")
      (value "470pF")
      (footprint "CAPC1005X33N")
      (description "Capacitor ceramic, C0G (NP0), 470pF, 50V, 5%, -55 to +125 C, EIA0402")
      (fields
        (field (name "TOLERANCE") "5%")
        (field (name "VOLTAGE") "50V")
        (field (name "Comment") "CAPACITOR_NP_TYPE1")
      )
      (libsource (lib "parts") (part "CAPACITOR_NP_TYPE1"))
    )
    (comp (ref "C159")
      (value "47uF")
      (footprint "CAPC2013X125N")
      (description "Capacitor ceramic, X5R, 47uF, 6.3V, 20%, -55 to +85 C,")
      (fields
        (field (name "TOLERANCE") "20%")
        (field (name "VOLTAGE") "6.3V")
        (field (name "Comment") "CAPACITOR_NP_TYPE1")
      )
      (libsource (lib "parts") (part "CAPACITOR_NP_TYPE1"))
    )
    (comp (ref "C160")
      (value "0.47uF")
      (footprint "CAPC1005X55N")
      (description "Capacitor ceramic, X5R, 0.47uF, 10V, 10%, -55 to +85 C, EIA0402")
      (fields
        (field (name "TOLERANCE") "10%")
        (field (name "VOLTAGE") "10V")
        (field (name "Comment") "CAPACITOR_NP_TYPE1")
      )
      (libsource (lib "parts") (part "CAPACITOR_NP_TYPE1"))
    )
    (comp (ref "C161")
      (value "0.47uF")
      (footprint "CAPC1005X55N")
      (description "Capacitor ceramic, X5R, 0.47uF, 10V, 10%, -55 to +85 C, EIA0402")
      (fields
        (field (name "TOLERANCE") "10%")
        (field (name "VOLTAGE") "10V")
        (field (name "Comment") "CAPACITOR_NP_TYPE1")
      )
      (libsource (lib "parts") (part "CAPACITOR_NP_TYPE1"))
    )
    (comp (ref "C162")
      (value "0.47uF")
      (footprint "CAPC1005X55N")
      (description "Capacitor ceramic, X5R, 0.47uF, 10V, 10%, -55 to +85 C, EIA0402")
      (fields
        (field (name "TOLERANCE") "10%")
        (field (name "VOLTAGE") "10V")
        (field (name "Comment") "CAPACITOR_NP_TYPE1")
      )
      (libsource (lib "parts") (part "CAPACITOR_NP_TYPE1"))
    )
    (comp (ref "C163")
      (value "0.47uF")
      (footprint "CAPC1005X55N")
      (description "Capacitor ceramic, X5R, 0.47uF, 10V, 10%, -55 to +85 C, EIA0402")
      (fields
        (field (name "TOLERANCE") "10%")
        (field (name "VOLTAGE") "10V")
        (field (name "Comment") "CAPACITOR_NP_TYPE1")
      )
      (libsource (lib "parts") (part "CAPACITOR_NP_TYPE1"))
    )
    (comp (ref "C164")
      (value "0.47uF")
      (footprint "CAPC1005X55N")
      (description "Capacitor ceramic, X5R, 0.47uF, 10V, 10%, -55 to +85 C, EIA0402")
      (fields
        (field (name "TOLERANCE") "10%")
        (field (name "VOLTAGE") "10V")
        (field (name "Comment") "CAPACITOR_NP_TYPE1")
      )
      (libsource (lib "parts") (part "CAPACITOR_NP_TYPE1"))
    )
    (comp (ref "C165")
      (value "0.47uF")
      (footprint "CAPC1005X55N")
      (description "Capacitor ceramic, X5R, 0.47uF, 10V, 10%, -55 to +85 C, EIA0402")
      (fields
        (field (name "TOLERANCE") "10%")
        (field (name "VOLTAGE") "10V")
        (field (name "Comment") "CAPACITOR_NP_TYPE1")
      )
      (libsource (lib "parts") (part "CAPACITOR_NP_TYPE1"))
    )
    (comp (ref "C166")
      (value "0.47uF")
      (footprint "CAPC1005X55N")
      (description "Capacitor ceramic, X5R, 0.47uF, 10V, 10%, -55 to +85 C, EIA0402")
      (fields
        (field (name "TOLERANCE") "10%")
        (field (name "VOLTAGE") "10V")
        (field (name "Comment") "CAPACITOR_NP_TYPE1")
      )
      (libsource (lib "parts") (part "CAPACITOR_NP_TYPE1"))
    )
    (comp (ref "C167")
      (value "0.47uF")
      (footprint "CAPC1005X55N")
      (description "Capacitor ceramic, X5R, 0.47uF, 10V, 10%, -55 to +85 C, EIA0402")
      (fields
        (field (name "TOLERANCE") "10%")
        (field (name "VOLTAGE") "10V")
        (field (name "Comment") "CAPACITOR_NP_TYPE1")
      )
      (libsource (lib "parts") (part "CAPACITOR_NP_TYPE1"))
    )
    (comp (ref "C168")
      (value "0.47uF")
      (footprint "CAPC1005X55N")
      (description "Capacitor ceramic, X5R, 0.47uF, 10V, 10%, -55 to +85 C, EIA0402")
      (fields
        (field (name "TOLERANCE") "10%")
        (field (name "VOLTAGE") "10V")
        (field (name "Comment") "CAPACITOR_NP_TYPE1")
      )
      (libsource (lib "parts") (part "CAPACITOR_NP_TYPE1"))
    )
    (comp (ref "C169")
      (value "0.47uF")
      (footprint "CAPC1005X55N")
      (description "Capacitor ceramic, X5R, 0.47uF, 10V, 10%, -55 to +85 C, EIA0402")
      (fields
        (field (name "TOLERANCE") "10%")
        (field (name "VOLTAGE") "10V")
        (field (name "Comment") "CAPACITOR_NP_TYPE1")
      )
      (libsource (lib "parts") (part "CAPACITOR_NP_TYPE1"))
    )
    (comp (ref "C170")
      (value "0.47uF")
      (footprint "CAPC1005X55N")
      (description "Capacitor ceramic, X5R, 0.47uF, 10V, 10%, -55 to +85 C, EIA0402")
      (fields
        (field (name "TOLERANCE") "10%")
        (field (name "VOLTAGE") "10V")
        (field (name "Comment") "CAPACITOR_NP_TYPE1")
      )
      (libsource (lib "parts") (part "CAPACITOR_NP_TYPE1"))
    )
    (comp (ref "C171")
      (value "0.47uF")
      (footprint "CAPC1005X55N")
      (description "Capacitor ceramic, X5R, 0.47uF, 10V, 10%, -55 to +85 C, EIA0402")
      (fields
        (field (name "TOLERANCE") "10%")
        (field (name "VOLTAGE") "10V")
        (field (name "Comment") "CAPACITOR_NP_TYPE1")
      )
      (libsource (lib "parts") (part "CAPACITOR_NP_TYPE1"))
    )
    (comp (ref "C260")
      (value "0.47uF")
      (footprint "CAPC1005X55N")
      (description "Capacitor ceramic, X5R, 0.47uF, 10V, 10%, -55 to +85 C, EIA0402")
      (fields
        (field (name "TOLERANCE") "10%")
        (field (name "VOLTAGE") "10V")
        (field (name "Comment") "CAPACITOR_NP_TYPE1")
      )
      (libsource (lib "parts") (part "CAPACITOR_NP_TYPE1"))
    )
    (comp (ref "L3")
      (value "220 Ohm @ 100MHz")
      (footprint "INDC2012X85N")
      (description "Ferrite chip, 220 Ohm @ 100MHz, 2000mA, 25%, -55 to +125 C, 0805")
      (fields
        (field (name "TOLERANCE") "25%")
        (field (name "CURRENT") "2000mA")
        (field (name "MFG PART NUMBER 1") "BLM21PG221SN1D")
        (field (name "Comment") "INDUCTOR_CORE_TYPE1")
      )
      (libsource (lib "parts") (part "INDUCTOR_CORE_TYPE1"))
    )
    (comp (ref "L4")
      (value "220 Ohm @ 100MHz")
      (footprint "INDC2012X85N")
      (description "Ferrite chip, 220 Ohm @ 100MHz, 2000mA, 25%, -55 to +125 C, 0805")
      (fields
        (field (name "TOLERANCE") "25%")
        (field (name "CURRENT") "2000mA")
        (field (name "MFG PART NUMBER 1") "BLM21PG221SN1D")
        (field (name "Comment") "INDUCTOR_CORE_TYPE1")
      )
      (libsource (lib "parts") (part "INDUCTOR_CORE_TYPE1"))
    )
    (comp (ref "U1")
      (value "XC7Z020-1CLG484C")
      (footprint "CLG484")
      (description "667 MHz Zynq™-7000 AP SoC, 130 PS I/O, 200 FPGA I/O, 484-Ball BGA, Speed Grade 1, Commercial Grade")
      (fields (field (name "GENERIC PART NUMBER") "XC7Z020") (field (name "MANUFACTURER") "Xilinx"))
      (libsource (lib "parts") (part "XC7Z020-1CLG484C"))
    )
  )
  (nets
    (net (code "1") (name "1.0V") (class "Default")
      (node (ref "C102") (pin "1") (pinfunction "1_1") (pintype "passive"))
      (node (ref "C103") (pin "1") (pinfunction "1_1") (pintype "passive"))
      (node (ref "C104") (pin "1") (pinfunction "1_1") (pintype "passive"))
      (node (ref "C105") (pin "1") (pinfunction "1_1") (pintype "passive"))
      (node (ref "C106") (pin "1") (pinfunction "1_1") (pintype "passive"))
      (node (ref "C107") (pin "1") (pinfunction "1_1") (pintype "passive"))
      (node (ref "C108") (pin "1") (pinfunction "1_1") (pintype "passive"))
      (node (ref "C109") (pin "1") (pinfunction "1_1") (pintype "passive"))
      (node (ref "C110") (pin "1") (pinfunction "1_1") (pintype "passive"))
      (node (ref "C111") (pin "1") (pinfunction "1_1") (pintype "passive"))
      (node (ref "C112") (pin "1") (pinfunction "1_1") (pintype "passive"))
      (node (ref "C125") (pin "1") (pinfunction "1_1") (pintype "passive"))
      (node (ref "C126") (pin "1") (pinfunction "1_1") (pintype "passive"))
      (node (ref "C127") (pin "1") (pinfunction "1_1") (pintype "passive"))
      (node (ref "C128") (pin "1") (pinfunction "1_1") (pintype "passive"))
      (node (ref "C129") (pin "1") (pinfunction "1_1") (pintype "passive"))
      (node (ref "C130") (pin "1") (pinfunction "1_1") (pintype "passive"))
      (node (ref "C131") (pin "1") (pinfunction "1_1") (pintype "passive"))
      (node (ref "C132") (pin "1") (pinfunction "1_1") (pintype "passive"))
      (node (ref "C133") (pin "1") (pinfunction "1_1") (pintype "passive"))
      (node (ref "C134") (pin "1") (pinfunction "1_1") (pintype "passive"))
      (node (ref "C145") (pin "1") (pinfunction "1_1") (pintype "passive"))
      (node (ref "C146") (pin "1") (pinfunction "1_1") (pintype "passive"))
      (node (ref "C147") (pin "1") (pinfunction "1_1") (pintype "passive"))
      (node (ref "C148") (pin "1") (pinfunction "1_1") (pintype "passive"))
      (node (ref "C149") (pin "1") (pinfunction "1_1") (pintype "passive"))
      (node (ref "C160") (pin "1") (pinfunction "1_1") (pintype "passive"))
      (node (ref "C161") (pin "1") (pinfunction "1_1") (pintype "passive"))
      (node (ref "C162") (pin "1") (pinfunction "1_1") (pintype "passive"))
      (node (ref "C163") (pin "1") (pinfunction "1_1") (pintype "passive"))
      (node (ref "U1") (pin "G8") (pinfunction "VCCPINT_G8") (pintype "power_in"))
      (node (ref "U1") (pin "H11") (pinfunction "VCCBRAM_H11") (pintype "power_in"))
      (node (ref "U1") (pin "H9") (pinfunction "VCCPINT_H9") (pintype "power_in"))
      (node (ref "U1") (pin "J10") (pinfunction "VCCBRAM_J10") (pintype "power_in"))
      (node (ref "U1") (pin "J12") (pinfunction "VCCINT_J12") (pintype "power_in"))
      (node (ref "U1") (pin "J14") (pinfunction "VCCINT_J14") (pintype "power_in"))
      (node (ref "U1") (pin "J8") (pinfunction "VCCPINT_J8") (pintype "power_in"))
      (node (ref "U1") (pin "K13") (pinfunction "VCCINT_K13") (pintype "power_in"))
      (node (ref "U1") (pin "L14") (pinfunction "VCCINT_L14") (pintype "power_in"))
      (node (ref "U1") (pin "L8") (pinfunction "VCCPINT_L8") (pintype "power_in"))
      (node (ref "U1") (pin "M13") (pinfunction "VCCINT_M13") (pintype "power_in"))
      (node (ref "U1") (pin "N14") (pinfunction "VCCINT_N14") (pintype "power_in"))
      (node (ref "U1") (pin "N8") (pinfunction "VCCPINT_N8") (pintype "power_in"))
      (node (ref "U1") (pin "P13") (pinfunction "VCCINT_P13") (pintype "power_in"))
      (node (ref "U1") (pin "R14") (pinfunction "VCCINT_R14") (pintype "power_in"))
      (node (ref "U1") (pin "R8") (pinfunction "VCCPINT_R8") (pintype "power_in"))
    )
    (net (code "2") (name "1.5V") (class "Default")
      (node (ref "C153") (pin "1") (pinfunction "1_1") (pintype "passive"))
      (node (ref "C154") (pin "1") (pinfunction "1_1") (pintype "passive"))
      (node (ref "C155") (pin "1") (pinfunction "1_1") (pintype "passive"))
      (node (ref "C156") (pin "1") (pinfunction "1_1") (pintype "passive"))
      (node (ref "C157") (pin "1") (pinfunction "1_1") (pintype "passive"))
      (node (ref "C158") (pin "1") (pinfunction "1_1") (pintype "passive"))
      (node (ref "C167") (pin "1") (pinfunction "1_1") (pintype "passive"))
      (node (ref "C168") (pin "1") (pinfunction "1_1") (pintype "passive"))
      (node (ref "C169") (pin "1") (pinfunction "1_1") (pintype "passive"))
      (node (ref "C170") (pin "1") (pinfunction "1_1") (pintype "passive"))
      (node (ref "C171") (pin "1") (pinfunction "1_1") (pintype "passive"))
      (node (ref "U1") (pin "E2") (pinfunction "VCCO_DDR_502_E2") (pintype "power_in"))
      (node (ref "U1") (pin "F5") (pinfunction "VCCO_DDR_502_F5") (pintype "power_in"))
      (node (ref "U1") (pin "H1") (pinfunction "VCCO_DDR_502_H1") (pintype "power_in"))
      (node (ref "U1") (pin "J4") (pinfunction "VCCO_DDR_502_J4") (pintype "power_in"))
      (node (ref "U1") (pin "K7") (pinfunction "VCCO_DDR_502_K7") (pintype "power_in"))
      (node (ref "U1") (pin "M3") (pinfunction "VCCO_DDR_502_M3") (pintype "power_in"))
      (node (ref "U1") (pin "N6") (pinfunction "VCCO_DDR_502_N6") (pintype "power_in"))
      (node (ref "U1") (pin "R2") (pinfunction "VCCO_DDR_502_R2") (pintype "power_in"))
      (node (ref "U1") (pin "V1") (pinfunction "VCCO_DDR_502_V1") (pintype "power_in"))
    )
    (net (code "3") (name "1.8V") (class "Default")
      (node (ref "C113") (pin "1") (pinfunction "1_1") (pintype "passive"))
      (node (ref "C114") (pin "1") (pinfunction "1_1") (pintype "passive"))
      (node (ref "C115") (pin "1") (pinfunction "1_1") (pintype "passive"))
      (node (ref "C116") (pin "1") (pinfunction "1_1") (pintype "passive"))
      (node (ref "C150") (pin "1") (pinfunction "1_1") (pintype "passive"))
      (node (ref "C151") (pin "1") (pinfunction "1_1") (pintype "passive"))
      (node (ref "C152") (pin "1") (pinfunction "1_1") (pintype "passive"))
      (node (ref "C164") (pin "1") (pinfunction "1_1") (pintype "passive"))
      (node (ref "C165") (pin "1") (pinfunction "1_1") (pintype "passive"))
      (node (ref "C166") (pin "1") (pinfunction "1_1") (pintype "passive"))
      (node (ref "C73") (pin "1") (pinfunction "1_1") (pintype "passive"))
      (node (ref "L3") (pin "2") (pinfunction "2_2") (pintype "passive"))
      (node (ref "L4") (pin "2") (pinfunction "2_2") (pintype "passive"))
      (node (ref "U1") (pin "G9") (pinfunction "VCCBATT_0_G9") (pintype "power_in"))
      (node (ref "U1") (pin "K9") (pinfunction "VCCPAUX_K9") (pintype "power_in"))
      (node (ref "U1") (pin "L10") (pinfunction "VCCAUX_L10") (pintype "power_in"))
      (node (ref "U1") (pin "M9") (pinfunction "VCCPAUX_M9") (pintype "power_in"))
      (node (ref "U1") (pin "N10") (pinfunction "VCCAUX_N10") (pintype "power_in"))
      (node (ref "U1") (pin "P11") (pinfunction "VCCAUX_P11") (pintype "power_in"))
      (node (ref "U1") (pin "P9") (pinfunction "VCCPAUX_P9") (pintype "power_in"))
      (node (ref "U1") (pin "R10") (pinfunction "VCCAUX_R10") (pintype "power_in"))
      (node (ref "U1") (pin "T9") (pinfunction "VCCPAUX_T9") (pintype "power_in"))
    )
    (net (code "4") (name "1.8VADC") (class "Default")
      (node (ref "C74") (pin "1") (pinfunction "1_1") (pintype "passive"))
      (node (ref "C75") (pin "1") (pinfunction "1_1") (pintype "passive"))
      (node (ref "L4") (pin "1") (pinfunction "1_1") (pintype "passive"))
      (node (ref "U1") (pin "K11") (pinfunction "VCCADC_0_K11") (pintype "power_in"))
    )
    (net (code "5") (name "1.8VPLL") (class "Default")
      (node (ref "C260") (pin "1") (pinfunction "1_1") (pintype "passive"))
      (node (ref "C72") (pin "1") (pinfunction "1_1") (pintype "passive"))
      (node (ref "L3") (pin "1") (pinfunction "1_1") (pintype "passive"))
      (node (ref "U1") (pin "H10") (pinfunction "VCCPLL_H10") (pintype "power_in"))
    )
    (net (code "6") (name "3.3V") (class "Default")
      (node (ref "C159") (pin "1") (pinfunction "1_1") (pintype "passive"))
      (node (ref "C84") (pin "1") (pinfunction "1_1") (pintype "passive"))
      (node (ref "C85") (pin "1") (pinfunction "1_1") (pintype "passive"))
      (node (ref "C86") (pin "1") (pinfunction "1_1") (pintype "passive"))
      (node (ref "C87") (pin "1") (pinfunction "1_1") (pintype "passive"))
      (node (ref "C88") (pin "1") (pinfunction "1_1") (pintype "passive"))
      (node (ref "C89") (pin "1") (pinfunction "1_1") (pintype "passive"))
      (node (ref "C90") (pin "1") (pinfunction "1_1") (pintype "passive"))
      (node (ref "C91") (pin "1") (pinfunction "1_1") (pintype "passive"))
      (node (ref "U1") (pin "A10") (pinfunction "VCCO_MIO1_501_A10") (pintype "power_in"))
      (node (ref "U1") (pin "B13") (pinfunction "VCCO_MIO1_501_B13") (pintype "power_in"))
      (node (ref "U1") (pin "B3") (pinfunction "VCCO_MIO0_500_B3") (pintype "power_in"))
      (node (ref "U1") (pin "C6") (pinfunction "VCCO_MIO0_500_C6") (pintype "power_in"))
      (node (ref "U1") (pin "D9") (pinfunction "VCCO_MIO1_501_D9") (pintype "power_in"))
      (node (ref "U1") (pin "E12") (pinfunction "VCCO_MIO1_501_E12") (pintype "power_in"))
      (node (ref "U1") (pin "R12") (pinfunction "VCCO_0_R12") (pintype "power_in"))
      (node (ref "U1") (pin "T10") (pinfunction "RSVDVCC3_T10") (pintype "power_in"))
      (node (ref "U1") (pin "T7") (pinfunction "RSVDVCC1_T7") (pintype "power_in"))
      (node (ref "U1") (pin "T8") (pinfunction "RSVDVCC2_T8") (pintype "power_in"))
    )
    (net (code "7") (name "GND") (class "Default")
      (node (ref "C100") (pin "2") (pinfunction "2_2") (pintype "passive"))
      (node (ref "C101") (pin "2") (pinfunction "2_2") (pintype "passive"))
      (node (ref "C102") (pin "2") (pinfunction "2_2") (pintype "passive"))
      (node (ref "C103") (pin "2") (pinfunction "2_2") (pintype "passive"))
      (node (ref "C104") (pin "2") (pinfunction "2_2") (pintype "passive"))
      (node (ref "C105") (pin "2") (pinfunction "2_2") (pintype "passive"))
      (node (ref "C106") (pin "2") (pinfunction "2_2") (pintype "passive"))
      (node (ref "C107") (pin "2") (pinfunction "2_2") (pintype "passive"))
      (node (ref "C108") (pin "2") (pinfunction "2_2") (pintype "passive"))
      (node (ref "C109") (pin "2") (pinfunction "2_2") (pintype "passive"))
      (node (ref "C110") (pin "2") (pinfunction "2_2") (pintype "passive"))
      (node (ref "C111") (pin "2") (pinfunction "2_2") (pintype "passive"))
      (node (ref "C112") (pin "2") (pinfunction "2_2") (pintype "passive"))
      (node (ref "C113") (pin "2") (pinfunction "2_2") (pintype "passive"))
      (node (ref "C114") (pin "2") (pinfunction "2_2") (pintype "passive"))
      (node (ref "C115") (pin "2") (pinfunction "2_2") (pintype "passive"))
      (node (ref "C116") (pin "2") (pinfunction "2_2") (pintype "passive"))
      (node (ref "C117") (pin "2") (pinfunction "2_2") (pintype "passive"))
      (node (ref "C118") (pin "2") (pinfunction "2_2") (pintype "passive"))
      (node (ref "C119") (pin "2") (pinfunction "2_2") (pintype "passive"))
      (node (ref "C120") (pin "2") (pinfunction "2_2") (pintype "passive"))
      (node (ref "C121") (pin "2") (pinfunction "2_2") (pintype "passive"))
      (node (ref "C122") (pin "2") (pinfunction "2_2") (pintype "passive"))
      (node (ref "C123") (pin "2") (pinfunction "2_2") (pintype "passive"))
      (node (ref "C124") (pin "2") (pinfunction "2_2") (pintype "passive"))
      (node (ref "C125") (pin "2") (pinfunction "2_2") (pintype "passive"))
      (node (ref "C126") (pin "2") (pinfunction "2_2") (pintype "passive"))
      (node (ref "C127") (pin "2") (pinfunction "2_2") (pintype "passive"))
      (node (ref "C128") (pin "2") (pinfunction "2_2") (pintype "passive"))
      (node (ref "C129") (pin "2") (pinfunction "2_2") (pintype "passive"))
      (node (ref "C130") (pin "2") (pinfunction "2_2") (pintype "passive"))
      (node (ref "C131") (pin "2") (pinfunction "2_2") (pintype "passive"))
      (node (ref "C132") (pin "2") (pinfunction "2_2") (pintype "passive"))
      (node (ref "C133") (pin "2") (pinfunction "2_2") (pintype "passive"))
      (node (ref "C134") (pin "2") (pinfunction "2_2") (pintype "passive"))
      (node (ref "C135") (pin "2") (pinfunction "2_2") (pintype "passive"))
      (node (ref "C136") (pin "2") (pinfunction "2_2") (pintype "passive"))
      (node (ref "C137") (pin "2") (pinfunction "2_2") (pintype "passive"))
      (node (ref "C138") (pin "2") (pinfunction "2_2") (pintype "passive"))
      (node (ref "C139") (pin "2") (pinfunction "2_2") (pintype "passive"))
      (node (ref "C140") (pin "2") (pinfunction "2_2") (pintype "passive"))
      (node (ref "C141") (pin "2") (pinfunction "2_2") (pintype "passive"))
      (node (ref "C142") (pin "2") (pinfunction "2_2") (pintype "passive"))
      (node (ref "C143") (pin "2") (pinfunction "2_2") (pintype "passive"))
      (node (ref "C144") (pin "2") (pinfunction "2_2") (pintype "passive"))
      (node (ref "C145") (pin "2") (pinfunction "2_2") (pintype "passive"))
      (node (ref "C146") (pin "2") (pinfunction "2_2") (pintype "passive"))
      (node (ref "C147") (pin "2") (pinfunction "2_2") (pintype "passive"))
      (node (ref "C148") (pin "2") (pinfunction "2_2") (pintype "passive"))
      (node (ref "C149") (pin "2") (pinfunction "2_2") (pintype "passive"))
      (node (ref "C150") (pin "2") (pinfunction "2_2") (pintype "passive"))
      (node (ref "C151") (pin "2") (pinfunction "2_2") (pintype "passive"))
      (node (ref "C152") (pin "2") (pinfunction "2_2") (pintype "passive"))
      (node (ref "C153") (pin "2") (pinfunction "2_2") (pintype "passive"))
      (node (ref "C154") (pin "2") (pinfunction "2_2") (pintype "passive"))
      (node (ref "C155") (pin "2") (pinfunction "2_2") (pintype "passive"))
      (node (ref "C156") (pin "2") (pinfunction "2_2") (pintype "passive"))
      (node (ref "C157") (pin "2") (pinfunction "2_2") (pintype "passive"))
      (node (ref "C158") (pin "2") (pinfunction "2_2") (pintype "passive"))
      (node (ref "C159") (pin "2") (pinfunction "2_2") (pintype "passive"))
      (node (ref "C160") (pin "2") (pinfunction "2_2") (pintype "passive"))
      (node (ref "C161") (pin "2") (pinfunction "2_2") (pintype "passive"))
      (node (ref "C162") (pin "2") (pinfunction "2_2") (pintype "passive"))
      (node (ref "C163") (pin "2") (pinfunction "2_2") (pintype "passive"))
      (node (ref "C164") (pin "2") (pinfunction "2_2") (pintype "passive"))
      (node (ref "C165") (pin "2") (pinfunction "2_2") (pintype "passive"))
      (node (ref "C166") (pin "2") (pinfunction "2_2") (pintype "passive"))
      (node (ref "C167") (pin "2") (pinfunction "2_2") (pintype "passive"))
      (node (ref "C168") (pin "2") (pinfunction "2_2") (pintype "passive"))
      (node (ref "C169") (pin "2") (pinfunction "2_2") (pintype "passive"))
      (node (ref "C170") (pin "2") (pinfunction "2_2") (pintype "passive"))
      (node (ref "C171") (pin "2") (pinfunction "2_2") (pintype "passive"))
      (node (ref "C260") (pin "2") (pinfunction "2_2") (pintype "passive"))
      (node (ref "C72") (pin "2") (pinfunction "2_2") (pintype "passive"))
      (node (ref "C73") (pin "2") (pinfunction "2_2") (pintype "passive"))
      (node (ref "C74") (pin "2") (pinfunction "2_2") (pintype "passive"))
      (node (ref "C75") (pin "2") (pinfunction "2_2") (pintype "passive"))
      (node (ref "C76") (pin "2") (pinfunction "2_2") (pintype "passive"))
      (node (ref "C77") (pin "2") (pinfunction "2_2") (pintype "passive"))
      (node (ref "C78") (pin "2") (pinfunction "2_2") (pintype "passive"))
      (node (ref "C79") (pin "2") (pinfunction "2_2") (pintype "passive"))
      (node (ref "C80") (pin "2") (pinfunction "2_2") (pintype "passive"))
      (node (ref "C81") (pin "2") (pinfunction "2_2") (pintype "passive"))
      (node (ref "C82") (pin "2") (pinfunction "2_2") (pintype "passive"))
      (node (ref "C83") (pin "2") (pinfunction "2_2") (pintype "passive"))
      (node (ref "C84") (pin "2") (pinfunction "2_2") (pintype "passive"))
      (node (ref "C85") (pin "2") (pinfunction "2_2") (pintype "passive"))
      (node (ref "C86") (pin "2") (pinfunction "2_2") (pintype "passive"))
      (node (ref "C87") (pin "2") (pinfunction "2_2") (pintype "passive"))
      (node (ref "C88") (pin "2") (pinfunction "2_2") (pintype "passive"))
      (node (ref "C89") (pin "2") (pinfunction "2_2") (pintype "passive"))
      (node (ref "C90") (pin "2") (pinfunction "2_2") (pintype "passive"))
      (node (ref "C91") (pin "2") (pinfunction "2_2") (pintype "passive"))
      (node (ref "C92") (pin "2") (pinfunction "2_2") (pintype "passive"))
      (node (ref "C93") (pin "2") (pinfunction "2_2") (pintype "passive"))
      (node (ref "C94") (pin "2") (pinfunction "2_2") (pintype "passive"))
      (node (ref "C95") (pin "2") (pinfunction "2_2") (pintype "passive"))
      (node (ref "C96") (pin "2") (pinfunction "2_2") (pintype "passive"))
      (node (ref "C97") (pin "2") (pinfunction "2_2") (pintype "passive"))
      (node (ref "C98") (pin "2") (pinfunction "2_2") (pintype "passive"))
      (node (ref "C99") (pin "2") (pinfunction "2_2") (pintype "passive"))
      (node (ref "U1") (pin "A15") (pinfunction "GND_A15") (pintype "power_in"))
      (node (ref "U1") (pin "A5") (pinfunction "GND_A5") (pintype "power_in"))
      (node (ref "U1") (pin "AA15") (pinfunction "GND_AA15") (pintype "power_in"))
      (node (ref "U1") (pin "AA5") (pinfunction "GND_AA5") (pintype "power_in"))
      (node (ref "U1") (pin "AB18") (pinfunction "GND_AB18") (pintype "power_in"))
      (node (ref "U1") (pin "AB8") (pinfunction "GND_AB8") (pintype "power_in"))
      (node (ref "U1") (pin "B18") (pinfunction "GND_B18") (pintype "power_in"))
      (node (ref "U1") (pin "B8") (pinfunction "GND_B8") (pintype "power_in"))
      (node (ref "U1") (pin "C1") (pinfunction "GND_C1") (pintype "power_in"))
      (node (ref "U1") (pin "C11") (pinfunction "GND_C11") (pintype "power_in"))
      (node (ref "U1") (pin "C21") (pinfunction "GND_C21") (pintype "power_in"))
      (node (ref "U1") (pin "D14") (pinfunction "GND_D14") (pintype "power_in"))
      (node (ref "U1") (pin "D4") (pinfunction "GND_D4") (pintype "power_in"))
      (node (ref "U1") (pin "E17") (pinfunction "GND_E17") (pintype "power_in"))
      (node (ref "U1") (pin "E7") (pinfunction "GND_E7") (pintype "power_in"))
      (node (ref "U1") (pin "F10") (pinfunction "GND_F10") (pintype "power_in"))
      (node (ref "U1") (pin "F20") (pinfunction "GND_F20") (pintype "power_in"))
      (node (ref "U1") (pin "G10") (pinfunction "RSVDGND_G10") (pintype "power_in"))
      (node (ref "U1") (pin "G3") (pinfunction "GND_G3") (pintype "power_in"))
      (node (ref "U1") (pin "H12") (pinfunction "GND_H12") (pintype "power_in"))
      (node (ref "U1") (pin "H14") (pinfunction "GND_H14") (pintype "power_in"))
      (node (ref "U1") (pin "H16") (pinfunction "GND_H16") (pintype "power_in"))
      (node (ref "U1") (pin "H6") (pinfunction "GND_H6") (pintype "power_in"))
      (node (ref "U1") (pin "H8") (pinfunction "GND_H8") (pintype "power_in"))
      (node (ref "U1") (pin "J11") (pinfunction "GND_J11") (pintype "power_in"))
      (node (ref "U1") (pin "J13") (pinfunction "GND_J13") (pintype "power_in"))
      (node (ref "U1") (pin "J19") (pinfunction "GND_J19") (pintype "power_in"))
      (node (ref "U1") (pin "J9") (pinfunction "GND_J9") (pintype "power_in"))
      (node (ref "U1") (pin "K10") (pinfunction "GND_K10") (pintype "power_in"))
      (node (ref "U1") (pin "K12") (pinfunction "GNDADC_0_K12") (pintype "power_in"))
      (node (ref "U1") (pin "K14") (pinfunction "GND_K14") (pintype "power_in"))
      (node (ref "U1") (pin "K2") (pinfunction "GND_K2") (pintype "power_in"))
      (node (ref "U1") (pin "K22") (pinfunction "GND_K22") (pintype "power_in"))
      (node (ref "U1") (pin "K8") (pinfunction "GND_K8") (pintype "power_in"))
      (node (ref "U1") (pin "L13") (pinfunction "GND_L13") (pintype "power_in"))
      (node (ref "U1") (pin "L15") (pinfunction "GND_L15") (pintype "power_in"))
      (node (ref "U1") (pin "L5") (pinfunction "GND_L5") (pintype "power_in"))
      (node (ref "U1") (pin "L9") (pinfunction "GND_L9") (pintype "power_in"))
      (node (ref "U1") (pin "M10") (pinfunction "GND_M10") (pintype "power_in"))
      (node (ref "U1") (pin "M14") (pinfunction "GND_M14") (pintype "power_in"))
      (node (ref "U1") (pin "M18") (pinfunction "GND_M18") (pintype "power_in"))
      (node (ref "U1") (pin "M8") (pinfunction "GND_M8") (pintype "power_in"))
      (node (ref "U1") (pin "N1") (pinfunction "GND_N1") (pintype "power_in"))
      (node (ref "U1") (pin "N13") (pinfunction "GND_N13") (pintype "power_in"))
      (node (ref "U1") (pin "N21") (pinfunction "GND_N21") (pintype "power_in"))
      (node (ref "U1") (pin "N9") (pinfunction "GND_N9") (pintype "power_in"))
      (node (ref "U1") (pin "P10") (pinfunction "GND_P10") (pintype "power_in"))
      (node (ref "U1") (pin "P12") (pinfunction "GND_P12") (pintype "power_in"))
      (node (ref "U1") (pin "P14") (pinfunction "GND_P14") (pintype "power_in"))
      (node (ref "U1") (pin "P4") (pinfunction "GND_P4") (pintype "power_in"))
      (node (ref "U1") (pin "P8") (pinfunction "GND_P8") (pintype "power_in"))
      (node (ref "U1") (pin "R11") (pinfunction "GND_R11") (pintype "power_in"))
      (node (ref "U1") (pin "R13") (pinfunction "GND_R13") (pintype "power_in"))
      (node (ref "U1") (pin "R17") (pinfunction "GND_R17") (pintype "power_in"))
      (node (ref "U1") (pin "R9") (pinfunction "GND_R9") (pintype "power_in"))
      (node (ref "U1") (pin "T20") (pinfunction "GND_T20") (pintype "power_in"))
      (node (ref "U1") (pin "U13") (pinfunction "GND_U13") (pintype "power_in"))
      (node (ref "U1") (pin "U3") (pinfunction "GND_U3") (pintype "power_in"))
      (node (ref "U1") (pin "V16") (pinfunction "GND_V16") (pintype "power_in"))
      (node (ref "U1") (pin "V6") (pinfunction "GND_V6") (pintype "power_in"))
      (node (ref "U1") (pin "W19") (pinfunction "GND_W19") (pintype "power_in"))
      (node (ref "U1") (pin "W9") (pinfunction "GND_W9") (pintype "power_in"))
      (node (ref "U1") (pin "Y12") (pinfunction "GND_Y12") (pintype "power_in"))
      (node (ref "U1") (pin "Y2") (pinfunction "GND_Y2") (pintype "power_in"))
      (node (ref "U1") (pin "Y22") (pinfunction "GND_Y22") (pintype "power_in"))
    )
    (net (code "8") (name "VCCO_13") (class "Default")
      (node (ref "C76") (pin "1") (pinfunction "1_1") (pintype "passive"))
      (node (ref "C77") (pin "1") (pinfunction "1_1") (pintype "passive"))
      (node (ref "C78") (pin "1") (pinfunction "1_1") (pintype "passive"))
      (node (ref "C79") (pin "1") (pinfunction "1_1") (pintype "passive"))
      (node (ref "C92") (pin "1") (pinfunction "1_1") (pintype "passive"))
      (node (ref "C93") (pin "1") (pinfunction "1_1") (pintype "passive"))
      (node (ref "C94") (pin "1") (pinfunction "1_1") (pintype "passive"))
      (node (ref "C95") (pin "1") (pinfunction "1_1") (pintype "passive"))
      (node (ref "C96") (pin "1") (pinfunction "1_1") (pintype "passive"))
      (node (ref "U1") (pin "AA10") (pinfunction "VCCO_13_AA10") (pintype "power_in"))
      (node (ref "U1") (pin "AB3") (pinfunction "VCCO_13_AB3") (pintype "power_in"))
      (node (ref "U1") (pin "T5") (pinfunction "VCCO_13_T5") (pintype "power_in"))
      (node (ref "U1") (pin "U8") (pinfunction "VCCO_13_U8") (pintype "power_in"))
      (node (ref "U1") (pin "V11") (pinfunction "VCCO_13_V11") (pintype "power_in"))
      (node (ref "U1") (pin "W4") (pinfunction "VCCO_13_W4") (pintype "power_in"))
      (node (ref "U1") (pin "Y7") (pinfunction "VCCO_13_Y7") (pintype "power_in"))
    )
    (net (code "9") (name "VCCO_33") (class "Default")
      (node (ref "C117") (pin "1") (pinfunction "1_1") (pintype "passive"))
      (node (ref "C118") (pin "1") (pinfunction "1_1") (pintype "passive"))
      (node (ref "C119") (pin "1") (pinfunction "1_1") (pintype "passive"))
      (node (ref "C120") (pin "1") (pinfunction "1_1") (pintype "passive"))
      (node (ref "C135") (pin "1") (pinfunction "1_1") (pintype "passive"))
      (node (ref "C136") (pin "1") (pinfunction "1_1") (pintype "passive"))
      (node (ref "C137") (pin "1") (pinfunction "1_1") (pintype "passive"))
      (node (ref "C138") (pin "1") (pinfunction "1_1") (pintype "passive"))
      (node (ref "C139") (pin "1") (pinfunction "1_1") (pintype "passive"))
      (node (ref "U1") (pin "AA20") (pinfunction "VCCO_33_AA20") (pintype "power_in"))
      (node (ref "U1") (pin "AB13") (pinfunction "VCCO_33_AB13") (pintype "power_in"))
      (node (ref "U1") (pin "U18") (pinfunction "VCCO_33_U18") (pintype "power_in"))
      (node (ref "U1") (pin "V21") (pinfunction "VCCO_33_V21") (pintype "power_in"))
      (node (ref "U1") (pin "W14") (pinfunction "VCCO_33_W14") (pintype "power_in"))
      (node (ref "U1") (pin "Y17") (pinfunction "VCCO_33_Y17") (pintype "power_in"))
    )
    (net (code "10") (name "VCCO_34") (class "Default")
      (node (ref "C100") (pin "1") (pinfunction "1_1") (pintype "passive"))
      (node (ref "C101") (pin "1") (pinfunction "1_1") (pintype "passive"))
      (node (ref "C80") (pin "1") (pinfunction "1_1") (pintype "passive"))
      (node (ref "C81") (pin "1") (pinfunction "1_1") (pintype "passive"))
      (node (ref "C82") (pin "1") (pinfunction "1_1") (pintype "passive"))
      (node (ref "C83") (pin "1") (pinfunction "1_1") (pintype "passive"))
      (node (ref "C97") (pin "1") (pinfunction "1_1") (pintype "passive"))
      (node (ref "C98") (pin "1") (pinfunction "1_1") (pintype "passive"))
      (node (ref "C99") (pin "1") (pinfunction "1_1") (pintype "passive"))
      (node (ref "U1") (pin "K17") (pinfunction "VCCO_34_K17") (pintype "power_in"))
      (node (ref "U1") (pin "L20") (pinfunction "VCCO_34_L20") (pintype "power_in"))
      (node (ref "U1") (pin "N16") (pinfunction "VCCO_34_N16") (pintype "power_in"))
      (node (ref "U1") (pin "P19") (pinfunction "VCCO_34_P19") (pintype "power_in"))
      (node (ref "U1") (pin "R22") (pinfunction "VCCO_34_R22") (pintype "power_in"))
      (node (ref "U1") (pin "T15") (pinfunction "VCCO_34_T15") (pintype "power_in"))
    )
    (net (code "11") (name "VCCO_35") (class "Default")
      (node (ref "C121") (pin "1") (pinfunction "1_1") (pintype "passive"))
      (node (ref "C122") (pin "1") (pinfunction "1_1") (pintype "passive"))
      (node (ref "C123") (pin "1") (pinfunction "1_1") (pintype "passive"))
      (node (ref "C124") (pin "1") (pinfunction "1_1") (pintype "passive"))
      (node (ref "C140") (pin "1") (pinfunction "1_1") (pintype "passive"))
      (node (ref "C141") (pin "1") (pinfunction "1_1") (pintype "passive"))
      (node (ref "C142") (pin "1") (pinfunction "1_1") (pintype "passive"))
      (node (ref "C143") (pin "1") (pinfunction "1_1") (pintype "passive"))
      (node (ref "C144") (pin "1") (pinfunction "1_1") (pintype "passive"))
      (node (ref "U1") (pin "A20") (pinfunction "VCCO_35_A20") (pintype "power_in"))
      (node (ref "U1") (pin "C16") (pinfunction "VCCO_35_C16") (pintype "power_in"))
      (node (ref "U1") (pin "D19") (pinfunction "VCCO_35_D19") (pintype "power_in"))
      (node (ref "U1") (pin "E22") (pinfunction "VCCO_35_E22") (pintype "power_in"))
      (node (ref "U1") (pin "F15") (pinfunction "VCCO_35_F15") (pintype "power_in"))
      (node (ref "U1") (pin "G18") (pinfunction "VCCO_35_G18") (pintype "power_in"))
      (node (ref "U1") (pin "H21") (pinfunction "VCCO_35_H21") (pintype "power_in"))
    )
  )
)
